# uSupply_upgrade_control_board_v0001.net
KiCad netlist of a schematic drawn in EAGLE
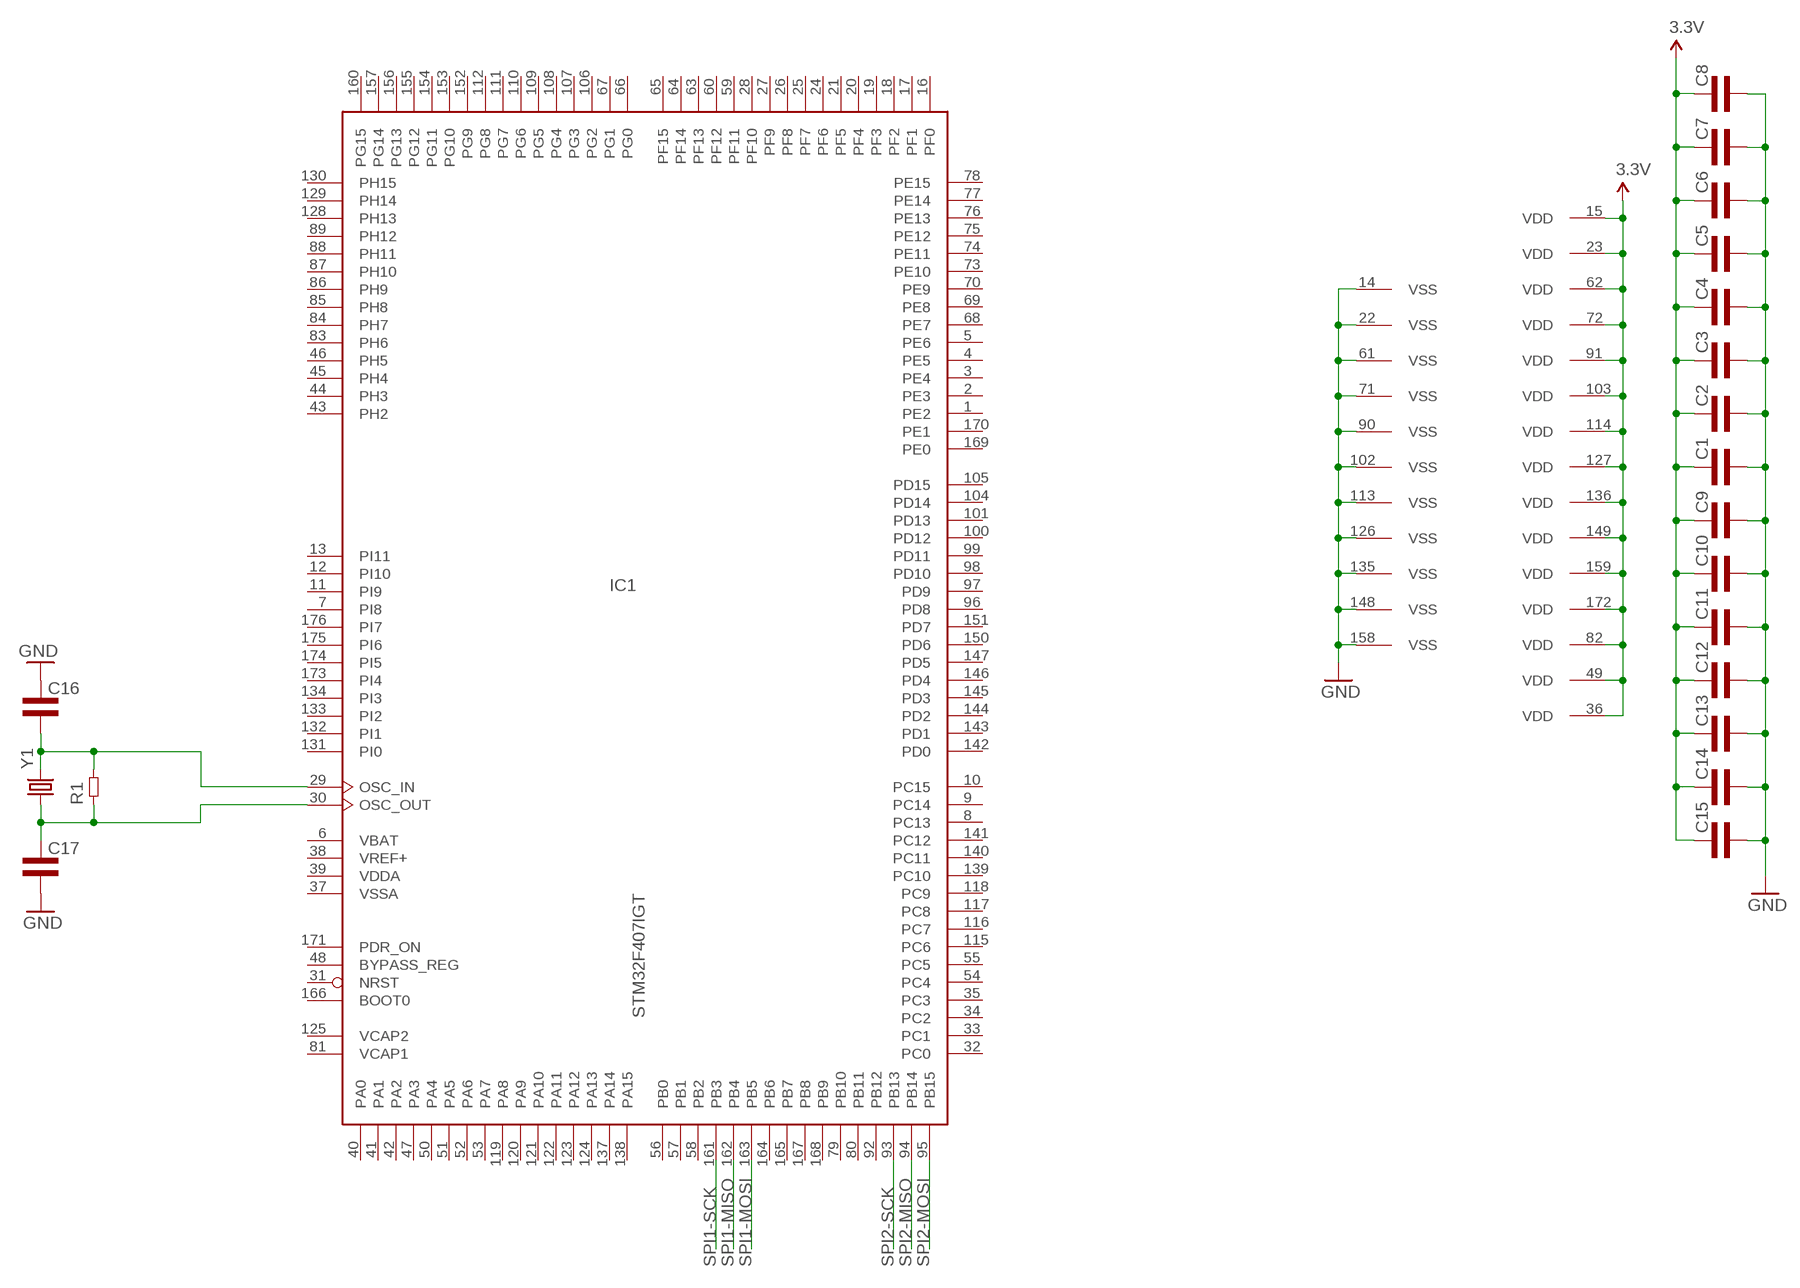
[diagram p0: schematic, sheet 1]

(export (version "E")
  (design (tool "Eeschema 10.0.6"))
  (components
    (comp (ref "C1")
      (value "CAP0402L3")
      (footprint "eagle-import:0402L3")
      (libsource (lib "eagle-import") (part "CAP0402L3"))
    )
    (comp (ref "C2")
      (value "CAP0402L3")
      (footprint "eagle-import:0402L3")
      (libsource (lib "eagle-import") (part "CAP0402L3"))
    )
    (comp (ref "C3")
      (value "CAP0402L3")
      (footprint "eagle-import:0402L3")
      (libsource (lib "eagle-import") (part "CAP0402L3"))
    )
    (comp (ref "C4")
      (value "CAP0402L3")
      (footprint "eagle-import:0402L3")
      (libsource (lib "eagle-import") (part "CAP0402L3"))
    )
    (comp (ref "C5")
      (value "CAP0402L3")
      (footprint "eagle-import:0402L3")
      (libsource (lib "eagle-import") (part "CAP0402L3"))
    )
    (comp (ref "C6")
      (value "CAP0402L3")
      (footprint "eagle-import:0402L3")
      (libsource (lib "eagle-import") (part "CAP0402L3"))
    )
    (comp (ref "C7")
      (value "CAP0402L3")
      (footprint "eagle-import:0402L3")
      (libsource (lib "eagle-import") (part "CAP0402L3"))
    )
    (comp (ref "C8")
      (value "CAP0402L3")
      (footprint "eagle-import:0402L3")
      (libsource (lib "eagle-import") (part "CAP0402L3"))
    )
    (comp (ref "C9")
      (value "CAP0402L3")
      (footprint "eagle-import:0402L3")
      (libsource (lib "eagle-import") (part "CAP0402L3"))
    )
    (comp (ref "C10")
      (value "CAP0402L3")
      (footprint "eagle-import:0402L3")
      (libsource (lib "eagle-import") (part "CAP0402L3"))
    )
    (comp (ref "C11")
      (value "CAP0402L3")
      (footprint "eagle-import:0402L3")
      (libsource (lib "eagle-import") (part "CAP0402L3"))
    )
    (comp (ref "C12")
      (value "CAP0402L3")
      (footprint "eagle-import:0402L3")
      (libsource (lib "eagle-import") (part "CAP0402L3"))
    )
    (comp (ref "C13")
      (value "CAP0402L3")
      (footprint "eagle-import:0402L3")
      (libsource (lib "eagle-import") (part "CAP0402L3"))
    )
    (comp (ref "C14")
      (value "CAP0402L3")
      (footprint "eagle-import:0402L3")
      (libsource (lib "eagle-import") (part "CAP0402L3"))
    )
    (comp (ref "C15")
      (value "CAP0402L3")
      (footprint "eagle-import:0402L3")
      (libsource (lib "eagle-import") (part "CAP0402L3"))
    )
    (comp (ref "C16")
      (value "CAP0402L3")
      (footprint "eagle-import:0402L3")
      (libsource (lib "eagle-import") (part "CAP0402L3"))
    )
    (comp (ref "C17")
      (value "CAP0402L3")
      (footprint "eagle-import:0402L3")
      (libsource (lib "eagle-import") (part "CAP0402L3"))
    )
    (comp (ref "IC1")
      (value "STM32F407IGT")
      (footprint "eagle-import:LQFP176")
      (libsource (lib "eagle-import") (part "STM32F407ITG"))
    )
    (comp (ref "R1")
      (value "RES0402L3")
      (footprint "eagle-import:0402L3")
      (libsource (lib "eagle-import") (part "RES0402L3"))
    )
    (comp (ref "Y1")
      (value "CRYSTALHC49US")
      (footprint "eagle-import:HC49US")
      (libsource (lib "eagle-import") (part "CRYSTALHC49US"))
    )
  )
  (nets
    (net (code "1") (name "/SPI1-MISO") (class "Default")
      (node (ref "IC1") (pin "162") (pinfunction "PB4_162") (pintype "bidirectional"))
    )
    (net (code "2") (name "/SPI1-MOSI") (class "Default")
      (node (ref "IC1") (pin "163") (pinfunction "PB5_163") (pintype "bidirectional"))
    )
    (net (code "3") (name "/SPI1-SCK") (class "Default")
      (node (ref "IC1") (pin "161") (pinfunction "PB3_161") (pintype "bidirectional"))
    )
    (net (code "4") (name "/SPI2-MISO") (class "Default")
      (node (ref "IC1") (pin "94") (pinfunction "PB14_94") (pintype "bidirectional"))
    )
    (net (code "5") (name "/SPI2-MOSI") (class "Default")
      (node (ref "IC1") (pin "95") (pinfunction "PB15_95") (pintype "bidirectional"))
    )
    (net (code "6") (name "/SPI2-SCK") (class "Default")
      (node (ref "IC1") (pin "93") (pinfunction "PB13_93") (pintype "bidirectional"))
    )
    (net (code "7") (name "/VBAT") (class "Default")
      (node (ref "IC1") (pin "6") (pinfunction "VBAT_6") (pintype "power_in"))
    )
    (net (code "8") (name "/VCAP1") (class "Default")
      (node (ref "IC1") (pin "81") (pinfunction "VCAP1_81") (pintype "power_in"))
    )
    (net (code "9") (name "/VCAP2") (class "Default")
      (node (ref "IC1") (pin "125") (pinfunction "VCAP2_125") (pintype "power_in"))
    )
    (net (code "10") (name "/VDDA") (class "Default")
      (node (ref "IC1") (pin "39") (pinfunction "VDDA_39") (pintype "power_in"))
    )
    (net (code "11") (name "/VREF+") (class "Default")
      (node (ref "IC1") (pin "38") (pinfunction "VREF+_38") (pintype "power_in"))
    )
    (net (code "12") (name "/VSSA") (class "Default")
      (node (ref "IC1") (pin "37") (pinfunction "VSSA_37") (pintype "power_in"))
    )
    (net (code "13") (name "3.3V") (class "Default")
      (node (ref "C1") (pin "P$1") (pinfunction "1_P$1") (pintype "bidirectional"))
      (node (ref "C10") (pin "P$1") (pinfunction "1_P$1") (pintype "bidirectional"))
      (node (ref "C11") (pin "P$1") (pinfunction "1_P$1") (pintype "bidirectional"))
      (node (ref "C12") (pin "P$1") (pinfunction "1_P$1") (pintype "bidirectional"))
      (node (ref "C13") (pin "P$1") (pinfunction "1_P$1") (pintype "bidirectional"))
      (node (ref "C14") (pin "P$1") (pinfunction "1_P$1") (pintype "bidirectional"))
      (node (ref "C15") (pin "P$1") (pinfunction "1_P$1") (pintype "bidirectional"))
      (node (ref "C2") (pin "P$1") (pinfunction "1_P$1") (pintype "bidirectional"))
      (node (ref "C3") (pin "P$1") (pinfunction "1_P$1") (pintype "bidirectional"))
      (node (ref "C4") (pin "P$1") (pinfunction "1_P$1") (pintype "bidirectional"))
      (node (ref "C5") (pin "P$1") (pinfunction "1_P$1") (pintype "bidirectional"))
      (node (ref "C6") (pin "P$1") (pinfunction "1_P$1") (pintype "bidirectional"))
      (node (ref "C7") (pin "P$1") (pinfunction "1_P$1") (pintype "bidirectional"))
      (node (ref "C8") (pin "P$1") (pinfunction "1_P$1") (pintype "bidirectional"))
      (node (ref "C9") (pin "P$1") (pinfunction "1_P$1") (pintype "bidirectional"))
      (node (ref "IC1") (pin "103") (pinfunction "VDD_103") (pintype "power_in"))
      (node (ref "IC1") (pin "114") (pinfunction "VDD_114") (pintype "power_in"))
      (node (ref "IC1") (pin "127") (pinfunction "VDD_127") (pintype "power_in"))
      (node (ref "IC1") (pin "136") (pinfunction "VDD_136") (pintype "power_in"))
      (node (ref "IC1") (pin "149") (pinfunction "VDD_149") (pintype "power_in"))
      (node (ref "IC1") (pin "15") (pinfunction "VDD_15") (pintype "power_in"))
      (node (ref "IC1") (pin "159") (pinfunction "VDD_159") (pintype "power_in"))
      (node (ref "IC1") (pin "172") (pinfunction "VDD_172") (pintype "power_in"))
      (node (ref "IC1") (pin "23") (pinfunction "VDD_23") (pintype "power_in"))
      (node (ref "IC1") (pin "36") (pinfunction "VDD_36") (pintype "power_in"))
      (node (ref "IC1") (pin "49") (pinfunction "VDD_49") (pintype "power_in"))
      (node (ref "IC1") (pin "62") (pinfunction "VDD_62") (pintype "power_in"))
      (node (ref "IC1") (pin "72") (pinfunction "VDD_72") (pintype "power_in"))
      (node (ref "IC1") (pin "82") (pinfunction "VDD_82") (pintype "power_in"))
      (node (ref "IC1") (pin "91") (pinfunction "VDD_91") (pintype "power_in"))
    )
    (net (code "14") (name "GND") (class "Default")
      (node (ref "C1") (pin "P$2") (pinfunction "2_P$2") (pintype "bidirectional"))
      (node (ref "C10") (pin "P$2") (pinfunction "2_P$2") (pintype "bidirectional"))
      (node (ref "C11") (pin "P$2") (pinfunction "2_P$2") (pintype "bidirectional"))
      (node (ref "C12") (pin "P$2") (pinfunction "2_P$2") (pintype "bidirectional"))
      (node (ref "C13") (pin "P$2") (pinfunction "2_P$2") (pintype "bidirectional"))
      (node (ref "C14") (pin "P$2") (pinfunction "2_P$2") (pintype "bidirectional"))
      (node (ref "C15") (pin "P$2") (pinfunction "2_P$2") (pintype "bidirectional"))
      (node (ref "C16") (pin "P$1") (pinfunction "1_P$1") (pintype "bidirectional"))
      (node (ref "C17") (pin "P$2") (pinfunction "2_P$2") (pintype "bidirectional"))
      (node (ref "C2") (pin "P$2") (pinfunction "2_P$2") (pintype "bidirectional"))
      (node (ref "C3") (pin "P$2") (pinfunction "2_P$2") (pintype "bidirectional"))
      (node (ref "C4") (pin "P$2") (pinfunction "2_P$2") (pintype "bidirectional"))
      (node (ref "C5") (pin "P$2") (pinfunction "2_P$2") (pintype "bidirectional"))
      (node (ref "C6") (pin "P$2") (pinfunction "2_P$2") (pintype "bidirectional"))
      (node (ref "C7") (pin "P$2") (pinfunction "2_P$2") (pintype "bidirectional"))
      (node (ref "C8") (pin "P$2") (pinfunction "2_P$2") (pintype "bidirectional"))
      (node (ref "C9") (pin "P$2") (pinfunction "2_P$2") (pintype "bidirectional"))
      (node (ref "IC1") (pin "102") (pinfunction "VSS_102") (pintype "power_in"))
      (node (ref "IC1") (pin "113") (pinfunction "VSS_113") (pintype "power_in"))
      (node (ref "IC1") (pin "126") (pinfunction "VSS_126") (pintype "power_in"))
      (node (ref "IC1") (pin "135") (pinfunction "VSS_135") (pintype "power_in"))
      (node (ref "IC1") (pin "14") (pinfunction "VSS_14") (pintype "power_in"))
      (node (ref "IC1") (pin "148") (pinfunction "VSS_148") (pintype "power_in"))
      (node (ref "IC1") (pin "158") (pinfunction "VSS_158") (pintype "power_in"))
      (node (ref "IC1") (pin "22") (pinfunction "VSS_22") (pintype "power_in"))
      (node (ref "IC1") (pin "61") (pinfunction "VSS_61") (pintype "power_in"))
      (node (ref "IC1") (pin "71") (pinfunction "VSS_71") (pintype "power_in"))
      (node (ref "IC1") (pin "90") (pinfunction "VSS_90") (pintype "power_in"))
    )
    (net (code "15") (name "Net-(C16-2)") (class "Default")
      (node (ref "C16") (pin "P$2") (pinfunction "2_P$2") (pintype "bidirectional"))
      (node (ref "IC1") (pin "29") (pinfunction "OSC_IN_29") (pintype "bidirectional"))
      (node (ref "R1") (pin "P$2") (pinfunction "2_P$2") (pintype "bidirectional"))
      (node (ref "Y1") (pin "2") (pinfunction "2_2") (pintype "passive"))
    )
    (net (code "16") (name "Net-(C17-1)") (class "Default")
      (node (ref "C17") (pin "P$1") (pinfunction "1_P$1") (pintype "bidirectional"))
      (node (ref "IC1") (pin "30") (pinfunction "OSC_OUT_30") (pintype "bidirectional"))
      (node (ref "R1") (pin "P$1") (pinfunction "1_P$1") (pintype "bidirectional"))
      (node (ref "Y1") (pin "1") (pinfunction "1_1") (pintype "passive"))
    )
    (net (code "17") (name "unconnected-(IC1A-BOOT0-Pad166)") (class "Default")
      (node (ref "IC1") (pin "166") (pinfunction "BOOT0_166") (pintype "input"))
    )
    (net (code "18") (name "unconnected-(IC1A-BYPASS_REG-Pad48)") (class "Default")
      (node (ref "IC1") (pin "48") (pinfunction "BYPASS_REG_48") (pintype "input"))
    )
    (net (code "19") (name "unconnected-(IC1A-NRST-Pad31)") (class "Default")
      (node (ref "IC1") (pin "31") (pinfunction "NRST_31") (pintype "bidirectional"))
    )
    (net (code "20") (name "unconnected-(IC1A-PA0-Pad40)") (class "Default")
      (node (ref "IC1") (pin "40") (pinfunction "PA0_40") (pintype "bidirectional"))
    )
    (net (code "21") (name "unconnected-(IC1A-PA1-Pad41)") (class "Default")
      (node (ref "IC1") (pin "41") (pinfunction "PA1_41") (pintype "bidirectional"))
    )
    (net (code "22") (name "unconnected-(IC1A-PA2-Pad42)") (class "Default")
      (node (ref "IC1") (pin "42") (pinfunction "PA2_42") (pintype "bidirectional"))
    )
    (net (code "23") (name "unconnected-(IC1A-PA3-Pad47)") (class "Default")
      (node (ref "IC1") (pin "47") (pinfunction "PA3_47") (pintype "bidirectional"))
    )
    (net (code "24") (name "unconnected-(IC1A-PA4-Pad50)") (class "Default")
      (node (ref "IC1") (pin "50") (pinfunction "PA4_50") (pintype "bidirectional"))
    )
    (net (code "25") (name "unconnected-(IC1A-PA5-Pad51)") (class "Default")
      (node (ref "IC1") (pin "51") (pinfunction "PA5_51") (pintype "bidirectional"))
    )
    (net (code "26") (name "unconnected-(IC1A-PA6-Pad52)") (class "Default")
      (node (ref "IC1") (pin "52") (pinfunction "PA6_52") (pintype "bidirectional"))
    )
    (net (code "27") (name "unconnected-(IC1A-PA7-Pad53)") (class "Default")
      (node (ref "IC1") (pin "53") (pinfunction "PA7_53") (pintype "bidirectional"))
    )
    (net (code "28") (name "unconnected-(IC1A-PA8-Pad119)") (class "Default")
      (node (ref "IC1") (pin "119") (pinfunction "PA8_119") (pintype "bidirectional"))
    )
    (net (code "29") (name "unconnected-(IC1A-PA9-Pad120)") (class "Default")
      (node (ref "IC1") (pin "120") (pinfunction "PA9_120") (pintype "bidirectional"))
    )
    (net (code "30") (name "unconnected-(IC1A-PA10-Pad121)") (class "Default")
      (node (ref "IC1") (pin "121") (pinfunction "PA10_121") (pintype "bidirectional"))
    )
    (net (code "31") (name "unconnected-(IC1A-PA11-Pad122)") (class "Default")
      (node (ref "IC1") (pin "122") (pinfunction "PA11_122") (pintype "bidirectional"))
    )
    (net (code "32") (name "unconnected-(IC1A-PA12-Pad123)") (class "Default")
      (node (ref "IC1") (pin "123") (pinfunction "PA12_123") (pintype "bidirectional"))
    )
    (net (code "33") (name "unconnected-(IC1A-PA13-Pad124)") (class "Default")
      (node (ref "IC1") (pin "124") (pinfunction "PA13_124") (pintype "bidirectional"))
    )
    (net (code "34") (name "unconnected-(IC1A-PA14-Pad137)") (class "Default")
      (node (ref "IC1") (pin "137") (pinfunction "PA14_137") (pintype "bidirectional"))
    )
    (net (code "35") (name "unconnected-(IC1A-PA15-Pad138)") (class "Default")
      (node (ref "IC1") (pin "138") (pinfunction "PA15_138") (pintype "bidirectional"))
    )
    (net (code "36") (name "unconnected-(IC1A-PB0-Pad56)") (class "Default")
      (node (ref "IC1") (pin "56") (pinfunction "PB0_56") (pintype "bidirectional"))
    )
    (net (code "37") (name "unconnected-(IC1A-PB1-Pad57)") (class "Default")
      (node (ref "IC1") (pin "57") (pinfunction "PB1_57") (pintype "bidirectional"))
    )
    (net (code "38") (name "unconnected-(IC1A-PB2-Pad58)") (class "Default")
      (node (ref "IC1") (pin "58") (pinfunction "PB2_58") (pintype "bidirectional"))
    )
    (net (code "39") (name "unconnected-(IC1A-PB6-Pad164)") (class "Default")
      (node (ref "IC1") (pin "164") (pinfunction "PB6_164") (pintype "bidirectional"))
    )
    (net (code "40") (name "unconnected-(IC1A-PB7-Pad165)") (class "Default")
      (node (ref "IC1") (pin "165") (pinfunction "PB7_165") (pintype "bidirectional"))
    )
    (net (code "41") (name "unconnected-(IC1A-PB8-Pad167)") (class "Default")
      (node (ref "IC1") (pin "167") (pinfunction "PB8_167") (pintype "bidirectional"))
    )
    (net (code "42") (name "unconnected-(IC1A-PB9-Pad168)") (class "Default")
      (node (ref "IC1") (pin "168") (pinfunction "PB9_168") (pintype "bidirectional"))
    )
    (net (code "43") (name "unconnected-(IC1A-PB10-Pad79)") (class "Default")
      (node (ref "IC1") (pin "79") (pinfunction "PB10_79") (pintype "bidirectional"))
    )
    (net (code "44") (name "unconnected-(IC1A-PB11-Pad80)") (class "Default")
      (node (ref "IC1") (pin "80") (pinfunction "PB11_80") (pintype "bidirectional"))
    )
    (net (code "45") (name "unconnected-(IC1A-PB12-Pad92)") (class "Default")
      (node (ref "IC1") (pin "92") (pinfunction "PB12_92") (pintype "bidirectional"))
    )
    (net (code "46") (name "unconnected-(IC1A-PC0-Pad32)") (class "Default")
      (node (ref "IC1") (pin "32") (pinfunction "PC0_32") (pintype "bidirectional"))
    )
    (net (code "47") (name "unconnected-(IC1A-PC1-Pad33)") (class "Default")
      (node (ref "IC1") (pin "33") (pinfunction "PC1_33") (pintype "bidirectional"))
    )
    (net (code "48") (name "unconnected-(IC1A-PC2-Pad34)") (class "Default")
      (node (ref "IC1") (pin "34") (pinfunction "PC2_34") (pintype "bidirectional"))
    )
    (net (code "49") (name "unconnected-(IC1A-PC3-Pad35)") (class "Default")
      (node (ref "IC1") (pin "35") (pinfunction "PC3_35") (pintype "bidirectional"))
    )
    (net (code "50") (name "unconnected-(IC1A-PC4-Pad54)") (class "Default")
      (node (ref "IC1") (pin "54") (pinfunction "PC4_54") (pintype "bidirectional"))
    )
    (net (code "51") (name "unconnected-(IC1A-PC5-Pad55)") (class "Default")
      (node (ref "IC1") (pin "55") (pinfunction "PC5_55") (pintype "bidirectional"))
    )
    (net (code "52") (name "unconnected-(IC1A-PC6-Pad115)") (class "Default")
      (node (ref "IC1") (pin "115") (pinfunction "PC6_115") (pintype "bidirectional"))
    )
    (net (code "53") (name "unconnected-(IC1A-PC7-Pad116)") (class "Default")
      (node (ref "IC1") (pin "116") (pinfunction "PC7_116") (pintype "bidirectional"))
    )
    (net (code "54") (name "unconnected-(IC1A-PC8-Pad117)") (class "Default")
      (node (ref "IC1") (pin "117") (pinfunction "PC8_117") (pintype "bidirectional"))
    )
    (net (code "55") (name "unconnected-(IC1A-PC9-Pad118)") (class "Default")
      (node (ref "IC1") (pin "118") (pinfunction "PC9_118") (pintype "bidirectional"))
    )
    (net (code "56") (name "unconnected-(IC1A-PC10-Pad139)") (class "Default")
      (node (ref "IC1") (pin "139") (pinfunction "PC10_139") (pintype "bidirectional"))
    )
    (net (code "57") (name "unconnected-(IC1A-PC11-Pad140)") (class "Default")
      (node (ref "IC1") (pin "140") (pinfunction "PC11_140") (pintype "bidirectional"))
    )
    (net (code "58") (name "unconnected-(IC1A-PC12-Pad141)") (class "Default")
      (node (ref "IC1") (pin "141") (pinfunction "PC12_141") (pintype "bidirectional"))
    )
    (net (code "59") (name "unconnected-(IC1A-PC13-Pad8)") (class "Default")
      (node (ref "IC1") (pin "8") (pinfunction "PC13_8") (pintype "bidirectional"))
    )
    (net (code "60") (name "unconnected-(IC1A-PC14-Pad9)") (class "Default")
      (node (ref "IC1") (pin "9") (pinfunction "PC14_9") (pintype "bidirectional"))
    )
    (net (code "61") (name "unconnected-(IC1A-PC15-Pad10)") (class "Default")
      (node (ref "IC1") (pin "10") (pinfunction "PC15_10") (pintype "bidirectional"))
    )
    (net (code "62") (name "unconnected-(IC1A-PD0-Pad142)") (class "Default")
      (node (ref "IC1") (pin "142") (pinfunction "PD0_142") (pintype "bidirectional"))
    )
    (net (code "63") (name "unconnected-(IC1A-PD1-Pad143)") (class "Default")
      (node (ref "IC1") (pin "143") (pinfunction "PD1_143") (pintype "bidirectional"))
    )
    (net (code "64") (name "unconnected-(IC1A-PD2-Pad144)") (class "Default")
      (node (ref "IC1") (pin "144") (pinfunction "PD2_144") (pintype "bidirectional"))
    )
    (net (code "65") (name "unconnected-(IC1A-PD3-Pad145)") (class "Default")
      (node (ref "IC1") (pin "145") (pinfunction "PD3_145") (pintype "bidirectional"))
    )
    (net (code "66") (name "unconnected-(IC1A-PD4-Pad146)") (class "Default")
      (node (ref "IC1") (pin "146") (pinfunction "PD4_146") (pintype "bidirectional"))
    )
    (net (code "67") (name "unconnected-(IC1A-PD5-Pad147)") (class "Default")
      (node (ref "IC1") (pin "147") (pinfunction "PD5_147") (pintype "bidirectional"))
    )
    (net (code "68") (name "unconnected-(IC1A-PD6-Pad150)") (class "Default")
      (node (ref "IC1") (pin "150") (pinfunction "PD6_150") (pintype "bidirectional"))
    )
    (net (code "69") (name "unconnected-(IC1A-PD7-Pad151)") (class "Default")
      (node (ref "IC1") (pin "151") (pinfunction "PD7_151") (pintype "bidirectional"))
    )
    (net (code "70") (name "unconnected-(IC1A-PD8-Pad96)") (class "Default")
      (node (ref "IC1") (pin "96") (pinfunction "PD8_96") (pintype "bidirectional"))
    )
    (net (code "71") (name "unconnected-(IC1A-PD9-Pad97)") (class "Default")
      (node (ref "IC1") (pin "97") (pinfunction "PD9_97") (pintype "bidirectional"))
    )
    (net (code "72") (name "unconnected-(IC1A-PD10-Pad98)") (class "Default")
      (node (ref "IC1") (pin "98") (pinfunction "PD10_98") (pintype "bidirectional"))
    )
    (net (code "73") (name "unconnected-(IC1A-PD11-Pad99)") (class "Default")
      (node (ref "IC1") (pin "99") (pinfunction "PD11_99") (pintype "bidirectional"))
    )
    (net (code "74") (name "unconnected-(IC1A-PD12-Pad100)") (class "Default")
      (node (ref "IC1") (pin "100") (pinfunction "PD12_100") (pintype "bidirectional"))
    )
    (net (code "75") (name "unconnected-(IC1A-PD13-Pad101)") (class "Default")
      (node (ref "IC1") (pin "101") (pinfunction "PD13_101") (pintype "bidirectional"))
    )
    (net (code "76") (name "unconnected-(IC1A-PD14-Pad104)") (class "Default")
      (node (ref "IC1") (pin "104") (pinfunction "PD14_104") (pintype "bidirectional"))
    )
    (net (code "77") (name "unconnected-(IC1A-PD15-Pad105)") (class "Default")
      (node (ref "IC1") (pin "105") (pinfunction "PD15_105") (pintype "bidirectional"))
    )
    (net (code "78") (name "unconnected-(IC1A-PDR_ON-Pad171)") (class "Default")
      (node (ref "IC1") (pin "171") (pinfunction "PDR_ON_171") (pintype "input"))
    )
    (net (code "79") (name "unconnected-(IC1A-PE0-Pad169)") (class "Default")
      (node (ref "IC1") (pin "169") (pinfunction "PE0_169") (pintype "bidirectional"))
    )
    (net (code "80") (name "unconnected-(IC1A-PE1-Pad170)") (class "Default")
      (node (ref "IC1") (pin "170") (pinfunction "PE1_170") (pintype "bidirectional"))
    )
    (net (code "81") (name "unconnected-(IC1A-PE2-Pad1)") (class "Default")
      (node (ref "IC1") (pin "1") (pinfunction "PE2_1") (pintype "bidirectional"))
    )
    (net (code "82") (name "unconnected-(IC1A-PE3-Pad2)") (class "Default")
      (node (ref "IC1") (pin "2") (pinfunction "PE3_2") (pintype "bidirectional"))
    )
    (net (code "83") (name "unconnected-(IC1A-PE4-Pad3)") (class "Default")
      (node (ref "IC1") (pin "3") (pinfunction "PE4_3") (pintype "bidirectional"))
    )
    (net (code "84") (name "unconnected-(IC1A-PE5-Pad4)") (class "Default")
      (node (ref "IC1") (pin "4") (pinfunction "PE5_4") (pintype "bidirectional"))
    )
    (net (code "85") (name "unconnected-(IC1A-PE6-Pad5)") (class "Default")
      (node (ref "IC1") (pin "5") (pinfunction "PE6_5") (pintype "bidirectional"))
    )
    (net (code "86") (name "unconnected-(IC1A-PE7-Pad68)") (class "Default")
      (node (ref "IC1") (pin "68") (pinfunction "PE7_68") (pintype "bidirectional"))
    )
    (net (code "87") (name "unconnected-(IC1A-PE8-Pad69)") (class "Default")
      (node (ref "IC1") (pin "69") (pinfunction "PE8_69") (pintype "bidirectional"))
    )
    (net (code "88") (name "unconnected-(IC1A-PE9-Pad70)") (class "Default")
      (node (ref "IC1") (pin "70") (pinfunction "PE9_70") (pintype "bidirectional"))
    )
    (net (code "89") (name "unconnected-(IC1A-PE10-Pad73)") (class "Default")
      (node (ref "IC1") (pin "73") (pinfunction "PE10_73") (pintype "bidirectional"))
    )
    (net (code "90") (name "unconnected-(IC1A-PE11-Pad74)") (class "Default")
      (node (ref "IC1") (pin "74") (pinfunction "PE11_74") (pintype "bidirectional"))
    )
    (net (code "91") (name "unconnected-(IC1A-PE12-Pad75)") (class "Default")
      (node (ref "IC1") (pin "75") (pinfunction "PE12_75") (pintype "bidirectional"))
    )
    (net (code "92") (name "unconnected-(IC1A-PE13-Pad76)") (class "Default")
      (node (ref "IC1") (pin "76") (pinfunction "PE13_76") (pintype "bidirectional"))
    )
    (net (code "93") (name "unconnected-(IC1A-PE14-Pad77)") (class "Default")
      (node (ref "IC1") (pin "77") (pinfunction "PE14_77") (pintype "bidirectional"))
    )
    (net (code "94") (name "unconnected-(IC1A-PE15-Pad78)") (class "Default")
      (node (ref "IC1") (pin "78") (pinfunction "PE15_78") (pintype "bidirectional"))
    )
    (net (code "95") (name "unconnected-(IC1A-PF0-Pad16)") (class "Default")
      (node (ref "IC1") (pin "16") (pinfunction "PF0_16") (pintype "bidirectional"))
    )
    (net (code "96") (name "unconnected-(IC1A-PF1-Pad17)") (class "Default")
      (node (ref "IC1") (pin "17") (pinfunction "PF1_17") (pintype "bidirectional"))
    )
    (net (code "97") (name "unconnected-(IC1A-PF2-Pad18)") (class "Default")
      (node (ref "IC1") (pin "18") (pinfunction "PF2_18") (pintype "bidirectional"))
    )
    (net (code "98") (name "unconnected-(IC1A-PF3-Pad19)") (class "Default")
      (node (ref "IC1") (pin "19") (pinfunction "PF3_19") (pintype "bidirectional"))
    )
    (net (code "99") (name "unconnected-(IC1A-PF4-Pad20)") (class "Default")
      (node (ref "IC1") (pin "20") (pinfunction "PF4_20") (pintype "bidirectional"))
    )
    (net (code "100") (name "unconnected-(IC1A-PF5-Pad21)") (class "Default")
      (node (ref "IC1") (pin "21") (pinfunction "PF5_21") (pintype "bidirectional"))
    )
    (net (code "101") (name "unconnected-(IC1A-PF6-Pad24)") (class "Default")
      (node (ref "IC1") (pin "24") (pinfunction "PF6_24") (pintype "bidirectional"))
    )
    (net (code "102") (name "unconnected-(IC1A-PF7-Pad25)") (class "Default")
      (node (ref "IC1") (pin "25") (pinfunction "PF7_25") (pintype "bidirectional"))
    )
    (net (code "103") (name "unconnected-(IC1A-PF8-Pad26)") (class "Default")
      (node (ref "IC1") (pin "26") (pinfunction "PF8_26") (pintype "bidirectional"))
    )
    (net (code "104") (name "unconnected-(IC1A-PF9-Pad27)") (class "Default")
      (node (ref "IC1") (pin "27") (pinfunction "PF9_27") (pintype "bidirectional"))
    )
    (net (code "105") (name "unconnected-(IC1A-PF10-Pad28)") (class "Default")
      (node (ref "IC1") (pin "28") (pinfunction "PF10_28") (pintype "bidirectional"))
    )
    (net (code "106") (name "unconnected-(IC1A-PF11-Pad59)") (class "Default")
      (node (ref "IC1") (pin "59") (pinfunction "PF11_59") (pintype "bidirectional"))
    )
    (net (code "107") (name "unconnected-(IC1A-PF12-Pad60)") (class "Default")
      (node (ref "IC1") (pin "60") (pinfunction "PF12_60") (pintype "bidirectional"))
    )
    (net (code "108") (name "unconnected-(IC1A-PF13-Pad63)") (class "Default")
      (node (ref "IC1") (pin "63") (pinfunction "PF13_63") (pintype "bidirectional"))
    )
    (net (code "109") (name "unconnected-(IC1A-PF14-Pad64)") (class "Default")
      (node (ref "IC1") (pin "64") (pinfunction "PF14_64") (pintype "bidirectional"))
    )
    (net (code "110") (name "unconnected-(IC1A-PF15-Pad65)") (class "Default")
      (node (ref "IC1") (pin "65") (pinfunction "PF15_65") (pintype "bidirectional"))
    )
    (net (code "111") (name "unconnected-(IC1A-PG0-Pad66)") (class "Default")
      (node (ref "IC1") (pin "66") (pinfunction "PG0_66") (pintype "bidirectional"))
    )
    (net (code "112") (name "unconnected-(IC1A-PG1-Pad67)") (class "Default")
      (node (ref "IC1") (pin "67") (pinfunction "PG1_67") (pintype "bidirectional"))
    )
    (net (code "113") (name "unconnected-(IC1A-PG2-Pad106)") (class "Default")
      (node (ref "IC1") (pin "106") (pinfunction "PG2_106") (pintype "bidirectional"))
    )
    (net (code "114") (name "unconnected-(IC1A-PG3-Pad107)") (class "Default")
      (node (ref "IC1") (pin "107") (pinfunction "PG3_107") (pintype "bidirectional"))
    )
    (net (code "115") (name "unconnected-(IC1A-PG4-Pad108)") (class "Default")
      (node (ref "IC1") (pin "108") (pinfunction "PG4_108") (pintype "bidirectional"))
    )
    (net (code "116") (name "unconnected-(IC1A-PG5-Pad109)") (class "Default")
      (node (ref "IC1") (pin "109") (pinfunction "PG5_109") (pintype "bidirectional"))
    )
    (net (code "117") (name "unconnected-(IC1A-PG6-Pad110)") (class "Default")
      (node (ref "IC1") (pin "110") (pinfunction "PG6_110") (pintype "bidirectional"))
    )
    (net (code "118") (name "unconnected-(IC1A-PG7-Pad111)") (class "Default")
      (node (ref "IC1") (pin "111") (pinfunction "PG7_111") (pintype "bidirectional"))
    )
    (net (code "119") (name "unconnected-(IC1A-PG8-Pad112)") (class "Default")
      (node (ref "IC1") (pin "112") (pinfunction "PG8_112") (pintype "bidirectional"))
    )
    (net (code "120") (name "unconnected-(IC1A-PG9-Pad152)") (class "Default")
      (node (ref "IC1") (pin "152") (pinfunction "PG9_152") (pintype "bidirectional"))
    )
    (net (code "121") (name "unconnected-(IC1A-PG10-Pad153)") (class "Default")
      (node (ref "IC1") (pin "153") (pinfunction "PG10_153") (pintype "bidirectional"))
    )
    (net (code "122") (name "unconnected-(IC1A-PG11-Pad154)") (class "Default")
      (node (ref "IC1") (pin "154") (pinfunction "PG11_154") (pintype "bidirectional"))
    )
    (net (code "123") (name "unconnected-(IC1A-PG12-Pad155)") (class "Default")
      (node (ref "IC1") (pin "155") (pinfunction "PG12_155") (pintype "bidirectional"))
    )
    (net (code "124") (name "unconnected-(IC1A-PG13-Pad156)") (class "Default")
      (node (ref "IC1") (pin "156") (pinfunction "PG13_156") (pintype "bidirectional"))
    )
    (net (code "125") (name "unconnected-(IC1A-PG14-Pad157)") (class "Default")
      (node (ref "IC1") (pin "157") (pinfunction "PG14_157") (pintype "bidirectional"))
    )
    (net (code "126") (name "unconnected-(IC1A-PG15-Pad160)") (class "Default")
      (node (ref "IC1") (pin "160") (pinfunction "PG15_160") (pintype "bidirectional"))
    )
    (net (code "127") (name "unconnected-(IC1A-PH2-Pad43)") (class "Default")
      (node (ref "IC1") (pin "43") (pinfunction "PH2_43") (pintype "bidirectional"))
    )
    (net (code "128") (name "unconnected-(IC1A-PH3-Pad44)") (class "Default")
      (node (ref "IC1") (pin "44") (pinfunction "PH3_44") (pintype "bidirectional"))
    )
    (net (code "129") (name "unconnected-(IC1A-PH4-Pad45)") (class "Default")
      (node (ref "IC1") (pin "45") (pinfunction "PH4_45") (pintype "bidirectional"))
    )
    (net (code "130") (name "unconnected-(IC1A-PH5-Pad46)") (class "Default")
      (node (ref "IC1") (pin "46") (pinfunction "PH5_46") (pintype "bidirectional"))
    )
    (net (code "131") (name "unconnected-(IC1A-PH6-Pad83)") (class "Default")
      (node (ref "IC1") (pin "83") (pinfunction "PH6_83") (pintype "bidirectional"))
    )
    (net (code "132") (name "unconnected-(IC1A-PH7-Pad84)") (class "Default")
      (node (ref "IC1") (pin "84") (pinfunction "PH7_84") (pintype "bidirectional"))
    )
    (net (code "133") (name "unconnected-(IC1A-PH8-Pad85)") (class "Default")
      (node (ref "IC1") (pin "85") (pinfunction "PH8_85") (pintype "bidirectional"))
    )
    (net (code "134") (name "unconnected-(IC1A-PH9-Pad86)") (class "Default")
      (node (ref "IC1") (pin "86") (pinfunction "PH9_86") (pintype "bidirectional"))
    )
    (net (code "135") (name "unconnected-(IC1A-PH10-Pad87)") (class "Default")
      (node (ref "IC1") (pin "87") (pinfunction "PH10_87") (pintype "bidirectional"))
    )
    (net (code "136") (name "unconnected-(IC1A-PH11-Pad88)") (class "Default")
      (node (ref "IC1") (pin "88") (pinfunction "PH11_88") (pintype "bidirectional"))
    )
    (net (code "137") (name "unconnected-(IC1A-PH12-Pad89)") (class "Default")
      (node (ref "IC1") (pin "89") (pinfunction "PH12_89") (pintype "bidirectional"))
    )
    (net (code "138") (name "unconnected-(IC1A-PH13-Pad128)") (class "Default")
      (node (ref "IC1") (pin "128") (pinfunction "PH13_128") (pintype "bidirectional"))
    )
    (net (code "139") (name "unconnected-(IC1A-PH14-Pad129)") (class "Default")
      (node (ref "IC1") (pin "129") (pinfunction "PH14_129") (pintype "bidirectional"))
    )
    (net (code "140") (name "unconnected-(IC1A-PH15-Pad130)") (class "Default")
      (node (ref "IC1") (pin "130") (pinfunction "PH15_130") (pintype "bidirectional"))
    )
    (net (code "141") (name "unconnected-(IC1A-PI0-Pad131)") (class "Default")
      (node (ref "IC1") (pin "131") (pinfunction "PI0_131") (pintype "bidirectional"))
    )
    (net (code "142") (name "unconnected-(IC1A-PI1-Pad132)") (class "Default")
      (node (ref "IC1") (pin "132") (pinfunction "PI1_132") (pintype "bidirectional"))
    )
    (net (code "143") (name "unconnected-(IC1A-PI2-Pad133)") (class "Default")
      (node (ref "IC1") (pin "133") (pinfunction "PI2_133") (pintype "bidirectional"))
    )
    (net (code "144") (name "unconnected-(IC1A-PI3-Pad134)") (class "Default")
      (node (ref "IC1") (pin "134") (pinfunction "PI3_134") (pintype "bidirectional"))
    )
    (net (code "145") (name "unconnected-(IC1A-PI4-Pad173)") (class "Default")
      (node (ref "IC1") (pin "173") (pinfunction "PI4_173") (pintype "bidirectional"))
    )
    (net (code "146") (name "unconnected-(IC1A-PI5-Pad174)") (class "Default")
      (node (ref "IC1") (pin "174") (pinfunction "PI5_174") (pintype "bidirectional"))
    )
    (net (code "147") (name "unconnected-(IC1A-PI6-Pad175)") (class "Default")
      (node (ref "IC1") (pin "175") (pinfunction "PI6_175") (pintype "bidirectional"))
    )
    (net (code "148") (name "unconnected-(IC1A-PI7-Pad176)") (class "Default")
      (node (ref "IC1") (pin "176") (pinfunction "PI7_176") (pintype "bidirectional"))
    )
    (net (code "149") (name "unconnected-(IC1A-PI8-Pad7)") (class "Default")
      (node (ref "IC1") (pin "7") (pinfunction "PI8_7") (pintype "bidirectional"))
    )
    (net (code "150") (name "unconnected-(IC1A-PI9-Pad11)") (class "Default")
      (node (ref "IC1") (pin "11") (pinfunction "PI9_11") (pintype "bidirectional"))
    )
    (net (code "151") (name "unconnected-(IC1A-PI10-Pad12)") (class "Default")
      (node (ref "IC1") (pin "12") (pinfunction "PI10_12") (pintype "bidirectional"))
    )
    (net (code "152") (name "unconnected-(IC1A-PI11-Pad13)") (class "Default")
      (node (ref "IC1") (pin "13") (pinfunction "PI11_13") (pintype "bidirectional"))
    )
  )
)
